# TemperatureACQ.net
KiCad netlist of a schematic drawn in Altium Designer
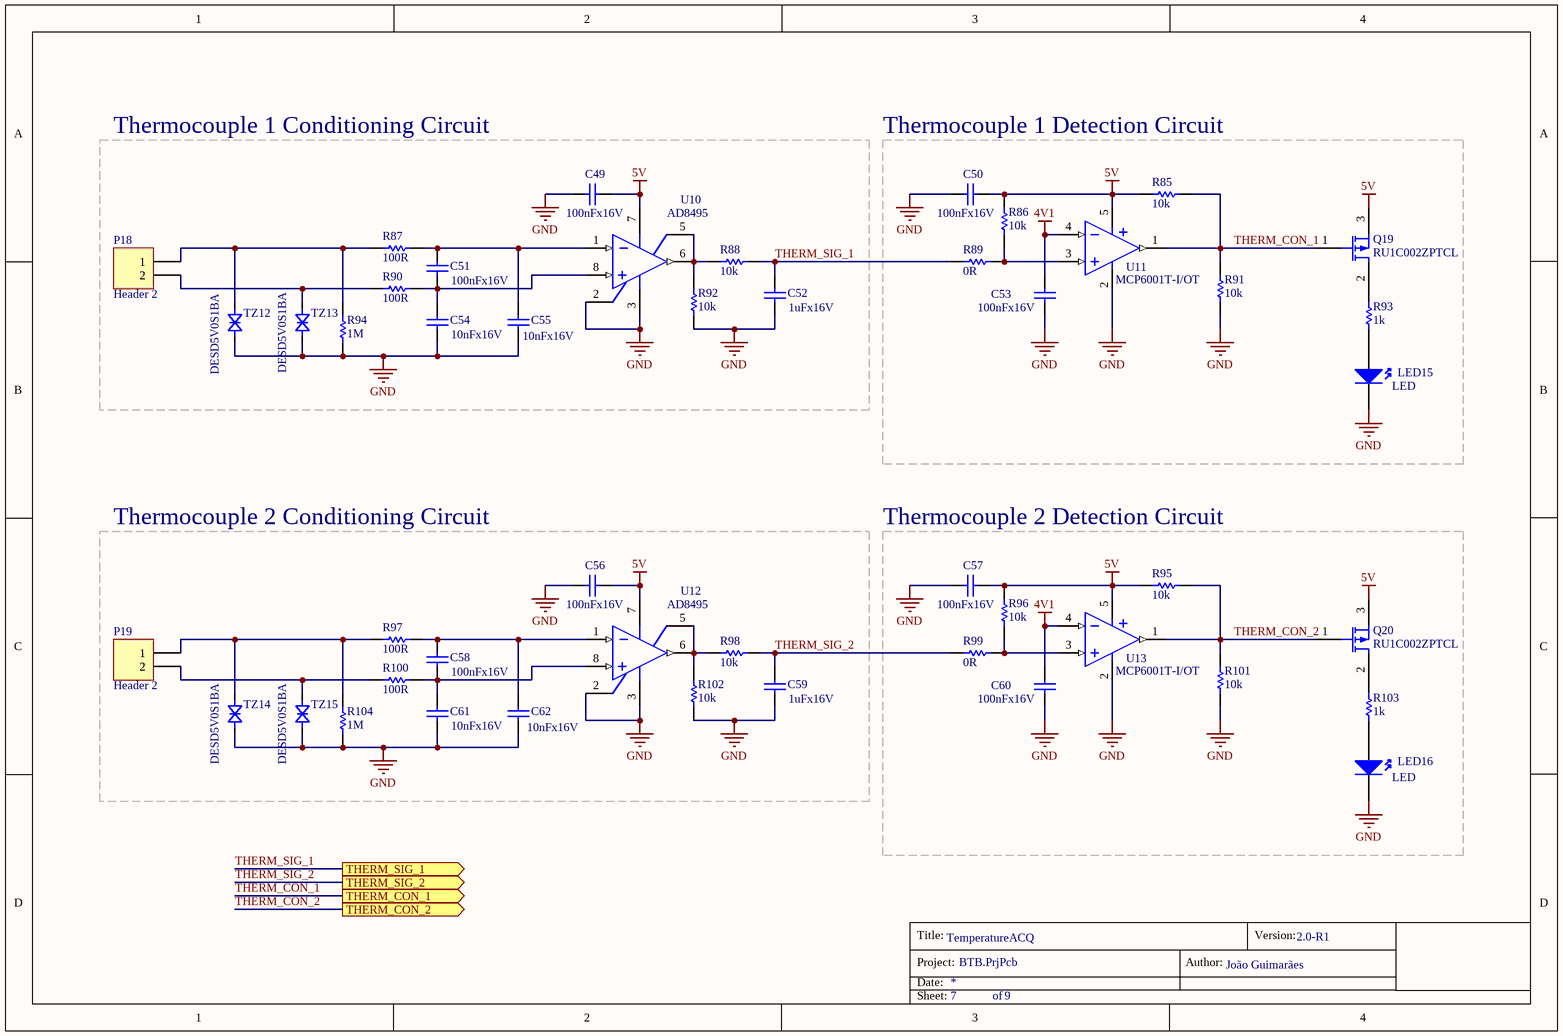
[diagram p0: TemperatureACQ.SchDoc]

(export (version "E")
  (design (tool "Eeschema 10.0.6"))
  (components
    (comp (ref "C49")
      (value "100nFx16V")
      (footprint "DISC-0805")
      (description "Capacitor")
      (libsource (lib "IntLib") (part "Cap"))
    )
    (comp (ref "C50")
      (value "100nFx16V")
      (footprint "DISC-0805")
      (description "Capacitor")
      (libsource (lib "IntLib") (part "Cap"))
    )
    (comp (ref "C51")
      (value "100nFx16V")
      (footprint "DISC-0805")
      (description "Capacitor")
      (libsource (lib "IntLib") (part "Cap"))
    )
    (comp (ref "C52")
      (value "1uFx16V")
      (footprint "DISC-0805")
      (description "Capacitor")
      (libsource (lib "IntLib") (part "Cap"))
    )
    (comp (ref "C53")
      (value "100nFx16V")
      (footprint "DISC-0805")
      (description "Capacitor")
      (libsource (lib "IntLib") (part "Cap"))
    )
    (comp (ref "C54")
      (value "10nFx16V")
      (footprint "DISC-0805")
      (description "Capacitor")
      (libsource (lib "IntLib") (part "Cap"))
    )
    (comp (ref "C55")
      (value "10nFx16V")
      (footprint "DISC-0805")
      (description "Capacitor")
      (libsource (lib "IntLib") (part "Cap"))
    )
    (comp (ref "C56")
      (value "100nFx16V")
      (footprint "DISC-0805")
      (description "Capacitor")
      (libsource (lib "IntLib") (part "Cap"))
    )
    (comp (ref "C57")
      (value "100nFx16V")
      (footprint "DISC-0805")
      (description "Capacitor")
      (libsource (lib "IntLib") (part "Cap"))
    )
    (comp (ref "C58")
      (value "100nFx16V")
      (footprint "DISC-0805")
      (description "Capacitor")
      (libsource (lib "IntLib") (part "Cap"))
    )
    (comp (ref "C59")
      (value "1uFx16V")
      (footprint "DISC-0805")
      (description "Capacitor")
      (libsource (lib "IntLib") (part "Cap"))
    )
    (comp (ref "C60")
      (value "100nFx16V")
      (footprint "DISC-0805")
      (description "Capacitor")
      (libsource (lib "IntLib") (part "Cap"))
    )
    (comp (ref "C61")
      (value "10nFx16V")
      (footprint "DISC-0805")
      (description "Capacitor")
      (libsource (lib "IntLib") (part "Cap"))
    )
    (comp (ref "C62")
      (value "10nFx16V")
      (footprint "DISC-0805")
      (description "Capacitor")
      (libsource (lib "IntLib") (part "Cap"))
    )
    (comp (ref "LED15") (value "LED") (footprint "DISC-LED-0.1-PTH") (libsource (lib "IntLib") (part "LED")))
    (comp (ref "LED16") (value "LED") (footprint "DISC-LED-0.1-PTH") (libsource (lib "IntLib") (part "LED")))
    (comp (ref "P18")
      (value "Header 2")
      (footprint "CON-FLEXWIRE-0.5MM2-1X2")
      (description "Header, 2-Pin")
      (fields (field (name "PUBLISHER") "Altium Limited"))
      (libsource (lib "IntLib") (part "Header 2"))
    )
    (comp (ref "P19")
      (value "Header 2")
      (footprint "CON-FLEXWIRE-0.5MM2-1X2")
      (description "Header, 2-Pin")
      (fields (field (name "PUBLISHER") "Altium Limited"))
      (libsource (lib "IntLib") (part "Header 2"))
    )
    (comp (ref "Q19")
      (value "RU1C002ZPTCL")
      (footprint "DISC-SOT-23")
      (description "P-Channel MOSFET")
      (libsource (lib "IntLib") (part "Transistor-PMOS"))
    )
    (comp (ref "Q20")
      (value "RU1C002ZPTCL")
      (footprint "DISC-SOT-23")
      (description "P-Channel MOSFET")
      (libsource (lib "IntLib") (part "Transistor-PMOS"))
    )
    (comp (ref "R85")
      (value "10k")
      (footprint "DISC-0805")
      (description "Resistor")
      (libsource (lib "IntLib") (part "Res"))
    )
    (comp (ref "R86")
      (value "10k")
      (footprint "DISC-0805")
      (description "Resistor")
      (libsource (lib "IntLib") (part "Res"))
    )
    (comp (ref "R87")
      (value "100R")
      (footprint "DISC-0805")
      (description "Resistor")
      (libsource (lib "IntLib") (part "Res"))
    )
    (comp (ref "R88")
      (value "10k")
      (footprint "DISC-0805")
      (description "Resistor")
      (libsource (lib "IntLib") (part "Res"))
    )
    (comp (ref "R89")
      (value "0R")
      (footprint "DISC-0805")
      (description "Resistor")
      (libsource (lib "IntLib") (part "Res"))
    )
    (comp (ref "R90")
      (value "100R")
      (footprint "DISC-0805")
      (description "Resistor")
      (libsource (lib "IntLib") (part "Res"))
    )
    (comp (ref "R91")
      (value "10k")
      (footprint "DISC-0805")
      (description "Resistor")
      (libsource (lib "IntLib") (part "Res"))
    )
    (comp (ref "R92")
      (value "10k")
      (footprint "DISC-0805")
      (description "Resistor")
      (libsource (lib "IntLib") (part "Res"))
    )
    (comp (ref "R93")
      (value "1k")
      (footprint "DISC-0805")
      (description "Resistor")
      (libsource (lib "IntLib") (part "Res"))
    )
    (comp (ref "R94")
      (value "1M")
      (footprint "DISC-0805")
      (description "Resistor")
      (libsource (lib "IntLib") (part "Res"))
    )
    (comp (ref "R95")
      (value "10k")
      (footprint "DISC-0805")
      (description "Resistor")
      (libsource (lib "IntLib") (part "Res"))
    )
    (comp (ref "R96")
      (value "10k")
      (footprint "DISC-0805")
      (description "Resistor")
      (libsource (lib "IntLib") (part "Res"))
    )
    (comp (ref "R97")
      (value "100R")
      (footprint "DISC-0805")
      (description "Resistor")
      (libsource (lib "IntLib") (part "Res"))
    )
    (comp (ref "R98")
      (value "10k")
      (footprint "DISC-0805")
      (description "Resistor")
      (libsource (lib "IntLib") (part "Res"))
    )
    (comp (ref "R99")
      (value "0R")
      (footprint "DISC-0805")
      (description "Resistor")
      (libsource (lib "IntLib") (part "Res"))
    )
    (comp (ref "R100")
      (value "100R")
      (footprint "DISC-0805")
      (description "Resistor")
      (libsource (lib "IntLib") (part "Res"))
    )
    (comp (ref "R101")
      (value "10k")
      (footprint "DISC-0805")
      (description "Resistor")
      (libsource (lib "IntLib") (part "Res"))
    )
    (comp (ref "R102")
      (value "10k")
      (footprint "DISC-0805")
      (description "Resistor")
      (libsource (lib "IntLib") (part "Res"))
    )
    (comp (ref "R103")
      (value "1k")
      (footprint "DISC-0805")
      (description "Resistor")
      (libsource (lib "IntLib") (part "Res"))
    )
    (comp (ref "R104")
      (value "1M")
      (footprint "DISC-0805")
      (description "Resistor")
      (libsource (lib "IntLib") (part "Res"))
    )
    (comp (ref "TZ12")
      (value "DESD5V0S1BA")
      (footprint "DISC-SOD-323")
      (description "TVZ-Bi-Directional")
      (libsource (lib "IntLib") (part "TVZ-Bi-Directional"))
    )
    (comp (ref "TZ13")
      (value "DESD5V0S1BA")
      (footprint "DISC-SOD-323")
      (description "TVZ-Bi-Directional")
      (libsource (lib "IntLib") (part "TVZ-Bi-Directional"))
    )
    (comp (ref "TZ14")
      (value "DESD5V0S1BA")
      (footprint "DISC-SOD-323")
      (description "TVZ-Bi-Directional")
      (libsource (lib "IntLib") (part "TVZ-Bi-Directional"))
    )
    (comp (ref "TZ15")
      (value "DESD5V0S1BA")
      (footprint "DISC-SOD-323")
      (description "TVZ-Bi-Directional")
      (libsource (lib "IntLib") (part "TVZ-Bi-Directional"))
    )
    (comp (ref "U10")
      (value "AD8495")
      (footprint "CI-MSOP-8")
      (description "Precision Type K Thermocouple Amplifier with Cold Junction Compensation")
      (libsource (lib "IntLib") (part "AD8495"))
    )
    (comp (ref "U11")
      (value "MCP6001T-I/OT")
      (footprint "CI-SOT-23-5")
      (description "Operational Amplifiers - Op Amps Single 1.8V 1MHz")
      (libsource (lib "IntLib") (part "MCP6001T-I/OT"))
    )
    (comp (ref "U12")
      (value "AD8495")
      (footprint "CI-MSOP-8")
      (description "Precision Type K Thermocouple Amplifier with Cold Junction Compensation")
      (libsource (lib "IntLib") (part "AD8495"))
    )
    (comp (ref "U13")
      (value "MCP6001T-I/OT")
      (footprint "CI-SOT-23-5")
      (description "Operational Amplifiers - Op Amps Single 1.8V 1MHz")
      (libsource (lib "IntLib") (part "MCP6001T-I/OT"))
    )
  )
  (nets
    (net (code "1") (name "/THERM_CON_1") (class "Default")
      (node (ref "Q19") (pin "1") (pinfunction "G_1") (pintype "passive"))
      (node (ref "R85") (pin "2") (pinfunction "2_2") (pintype "passive"))
      (node (ref "R91") (pin "1") (pinfunction "1_1") (pintype "passive"))
      (node (ref "U11") (pin "1") (pinfunction "Out_1") (pintype "output"))
    )
    (net (code "2") (name "/THERM_CON_2") (class "Default")
      (node (ref "Q20") (pin "1") (pinfunction "G_1") (pintype "passive"))
      (node (ref "R101") (pin "1") (pinfunction "1_1") (pintype "passive"))
      (node (ref "R95") (pin "2") (pinfunction "2_2") (pintype "passive"))
      (node (ref "U13") (pin "1") (pinfunction "Out_1") (pintype "output"))
    )
    (net (code "3") (name "/THERM_SIG_1") (class "Default")
      (node (ref "C52") (pin "2") (pinfunction "2_2") (pintype "passive"))
      (node (ref "R88") (pin "2") (pinfunction "2_2") (pintype "passive"))
      (node (ref "R89") (pin "1") (pinfunction "1_1") (pintype "passive"))
    )
    (net (code "4") (name "/THERM_SIG_2") (class "Default")
      (node (ref "C59") (pin "2") (pinfunction "2_2") (pintype "passive"))
      (node (ref "R98") (pin "2") (pinfunction "2_2") (pintype "passive"))
      (node (ref "R99") (pin "1") (pinfunction "1_1") (pintype "passive"))
    )
    (net (code "5") (name "4V1") (class "Default")
      (node (ref "C53") (pin "2") (pinfunction "2_2") (pintype "passive"))
      (node (ref "C60") (pin "2") (pinfunction "2_2") (pintype "passive"))
      (node (ref "U11") (pin "4") (pinfunction "IN-_4") (pintype "input"))
      (node (ref "U13") (pin "4") (pinfunction "IN-_4") (pintype "input"))
    )
    (net (code "6") (name "5V") (class "Default")
      (node (ref "C49") (pin "1") (pinfunction "1_1") (pintype "passive"))
      (node (ref "C50") (pin "2") (pinfunction "2_2") (pintype "passive"))
      (node (ref "C56") (pin "1") (pinfunction "1_1") (pintype "passive"))
      (node (ref "C57") (pin "2") (pinfunction "2_2") (pintype "passive"))
      (node (ref "Q19") (pin "3") (pinfunction "S_3") (pintype "passive"))
      (node (ref "Q20") (pin "3") (pinfunction "S_3") (pintype "passive"))
      (node (ref "R85") (pin "1") (pinfunction "1_1") (pintype "passive"))
      (node (ref "R86") (pin "1") (pinfunction "1_1") (pintype "passive"))
      (node (ref "R95") (pin "1") (pinfunction "1_1") (pintype "passive"))
      (node (ref "R96") (pin "1") (pinfunction "1_1") (pintype "passive"))
      (node (ref "U10") (pin "7") (pinfunction "V+_7") (pintype "power_in"))
      (node (ref "U11") (pin "5") (pinfunction "V+_5") (pintype "power_in"))
      (node (ref "U12") (pin "7") (pinfunction "V+_7") (pintype "power_in"))
      (node (ref "U13") (pin "5") (pinfunction "V+_5") (pintype "power_in"))
    )
    (net (code "7") (name "GND") (class "Default")
      (node (ref "C49") (pin "2") (pinfunction "2_2") (pintype "passive"))
      (node (ref "C50") (pin "1") (pinfunction "1_1") (pintype "passive"))
      (node (ref "C52") (pin "1") (pinfunction "1_1") (pintype "passive"))
      (node (ref "C53") (pin "1") (pinfunction "1_1") (pintype "passive"))
      (node (ref "C54") (pin "1") (pinfunction "1_1") (pintype "passive"))
      (node (ref "C55") (pin "1") (pinfunction "1_1") (pintype "passive"))
      (node (ref "C56") (pin "2") (pinfunction "2_2") (pintype "passive"))
      (node (ref "C57") (pin "1") (pinfunction "1_1") (pintype "passive"))
      (node (ref "C59") (pin "1") (pinfunction "1_1") (pintype "passive"))
      (node (ref "C60") (pin "1") (pinfunction "1_1") (pintype "passive"))
      (node (ref "C61") (pin "1") (pinfunction "1_1") (pintype "passive"))
      (node (ref "C62") (pin "1") (pinfunction "1_1") (pintype "passive"))
      (node (ref "LED15") (pin "2") (pinfunction "K_2") (pintype "passive"))
      (node (ref "LED16") (pin "2") (pinfunction "K_2") (pintype "passive"))
      (node (ref "R101") (pin "2") (pinfunction "2_2") (pintype "passive"))
      (node (ref "R102") (pin "2") (pinfunction "2_2") (pintype "passive"))
      (node (ref "R104") (pin "1") (pinfunction "1_1") (pintype "passive"))
      (node (ref "R91") (pin "2") (pinfunction "2_2") (pintype "passive"))
      (node (ref "R92") (pin "2") (pinfunction "2_2") (pintype "passive"))
      (node (ref "R94") (pin "1") (pinfunction "1_1") (pintype "passive"))
      (node (ref "TZ12") (pin "1") (pinfunction "A_1") (pintype "passive"))
      (node (ref "TZ13") (pin "1") (pinfunction "A_1") (pintype "passive"))
      (node (ref "TZ14") (pin "1") (pinfunction "A_1") (pintype "passive"))
      (node (ref "TZ15") (pin "1") (pinfunction "A_1") (pintype "passive"))
      (node (ref "U10") (pin "2") (pinfunction "REF_2") (pintype "passive"))
      (node (ref "U10") (pin "3") (pinfunction "V-_3") (pintype "power_in"))
      (node (ref "U11") (pin "2") (pinfunction "V-_2") (pintype "power_in"))
      (node (ref "U12") (pin "2") (pinfunction "REF_2") (pintype "passive"))
      (node (ref "U12") (pin "3") (pinfunction "V-_3") (pintype "power_in"))
      (node (ref "U13") (pin "2") (pinfunction "V-_2") (pintype "power_in"))
    )
    (net (code "8") (name "Net-(LED15-A)") (class "Default")
      (node (ref "LED15") (pin "1") (pinfunction "A_1") (pintype "passive"))
      (node (ref "R93") (pin "1") (pinfunction "1_1") (pintype "passive"))
    )
    (net (code "9") (name "Net-(LED16-A)") (class "Default")
      (node (ref "LED16") (pin "1") (pinfunction "A_1") (pintype "passive"))
      (node (ref "R103") (pin "1") (pinfunction "1_1") (pintype "passive"))
    )
    (net (code "10") (name "Net-(Q19-D)") (class "Default")
      (node (ref "Q19") (pin "2") (pinfunction "D_2") (pintype "passive"))
      (node (ref "R93") (pin "2") (pinfunction "2_2") (pintype "passive"))
    )
    (net (code "11") (name "Net-(Q20-D)") (class "Default")
      (node (ref "Q20") (pin "2") (pinfunction "D_2") (pintype "passive"))
      (node (ref "R103") (pin "2") (pinfunction "2_2") (pintype "passive"))
    )
    (net (code "12") (name "Net-(TZ12-K)") (class "Default")
      (node (ref "P18") (pin "1") (pinfunction "1_1") (pintype "passive"))
      (node (ref "R87") (pin "2") (pinfunction "2_2") (pintype "passive"))
      (node (ref "R94") (pin "2") (pinfunction "2_2") (pintype "passive"))
      (node (ref "TZ12") (pin "2") (pinfunction "K_2") (pintype "passive"))
    )
    (net (code "13") (name "Net-(TZ13-K)") (class "Default")
      (node (ref "P18") (pin "2") (pinfunction "2_2") (pintype "passive"))
      (node (ref "R90") (pin "2") (pinfunction "2_2") (pintype "passive"))
      (node (ref "TZ13") (pin "2") (pinfunction "K_2") (pintype "passive"))
    )
    (net (code "14") (name "Net-(TZ14-K)") (class "Default")
      (node (ref "P19") (pin "1") (pinfunction "1_1") (pintype "passive"))
      (node (ref "R104") (pin "2") (pinfunction "2_2") (pintype "passive"))
      (node (ref "R97") (pin "2") (pinfunction "2_2") (pintype "passive"))
      (node (ref "TZ14") (pin "2") (pinfunction "K_2") (pintype "passive"))
    )
    (net (code "15") (name "Net-(TZ15-K)") (class "Default")
      (node (ref "P19") (pin "2") (pinfunction "2_2") (pintype "passive"))
      (node (ref "R100") (pin "2") (pinfunction "2_2") (pintype "passive"))
      (node (ref "TZ15") (pin "2") (pinfunction "K_2") (pintype "passive"))
    )
    (net (code "16") (name "Net-(U10-IN+)") (class "Default")
      (node (ref "C51") (pin "1") (pinfunction "1_1") (pintype "passive"))
      (node (ref "C54") (pin "2") (pinfunction "2_2") (pintype "passive"))
      (node (ref "R90") (pin "1") (pinfunction "1_1") (pintype "passive"))
      (node (ref "U10") (pin "8") (pinfunction "IN+_8") (pintype "input"))
    )
    (net (code "17") (name "Net-(U10-IN-)") (class "Default")
      (node (ref "C51") (pin "2") (pinfunction "2_2") (pintype "passive"))
      (node (ref "C55") (pin "2") (pinfunction "2_2") (pintype "passive"))
      (node (ref "R87") (pin "1") (pinfunction "1_1") (pintype "passive"))
      (node (ref "U10") (pin "1") (pinfunction "IN-_1") (pintype "input"))
    )
    (net (code "18") (name "Net-(U10-OUT)") (class "Default")
      (node (ref "R88") (pin "1") (pinfunction "1_1") (pintype "passive"))
      (node (ref "R92") (pin "1") (pinfunction "1_1") (pintype "passive"))
      (node (ref "U10") (pin "5") (pinfunction "SENSE_5") (pintype "passive"))
      (node (ref "U10") (pin "6") (pinfunction "OUT_6") (pintype "output"))
    )
    (net (code "19") (name "Net-(U11-IN+)") (class "Default")
      (node (ref "R86") (pin "2") (pinfunction "2_2") (pintype "passive"))
      (node (ref "R89") (pin "2") (pinfunction "2_2") (pintype "passive"))
      (node (ref "U11") (pin "3") (pinfunction "IN+_3") (pintype "input"))
    )
    (net (code "20") (name "Net-(U12-IN+)") (class "Default")
      (node (ref "C58") (pin "1") (pinfunction "1_1") (pintype "passive"))
      (node (ref "C61") (pin "2") (pinfunction "2_2") (pintype "passive"))
      (node (ref "R100") (pin "1") (pinfunction "1_1") (pintype "passive"))
      (node (ref "U12") (pin "8") (pinfunction "IN+_8") (pintype "input"))
    )
    (net (code "21") (name "Net-(U12-IN-)") (class "Default")
      (node (ref "C58") (pin "2") (pinfunction "2_2") (pintype "passive"))
      (node (ref "C62") (pin "2") (pinfunction "2_2") (pintype "passive"))
      (node (ref "R97") (pin "1") (pinfunction "1_1") (pintype "passive"))
      (node (ref "U12") (pin "1") (pinfunction "IN-_1") (pintype "input"))
    )
    (net (code "22") (name "Net-(U12-OUT)") (class "Default")
      (node (ref "R102") (pin "1") (pinfunction "1_1") (pintype "passive"))
      (node (ref "R98") (pin "1") (pinfunction "1_1") (pintype "passive"))
      (node (ref "U12") (pin "5") (pinfunction "SENSE_5") (pintype "passive"))
      (node (ref "U12") (pin "6") (pinfunction "OUT_6") (pintype "output"))
    )
    (net (code "23") (name "Net-(U13-IN+)") (class "Default")
      (node (ref "R96") (pin "2") (pinfunction "2_2") (pintype "passive"))
      (node (ref "R99") (pin "2") (pinfunction "2_2") (pintype "passive"))
      (node (ref "U13") (pin "3") (pinfunction "IN+_3") (pintype "input"))
    )
  )
)
